# LTC6803_breakout.net
KiCad netlist of a schematic drawn in EAGLE
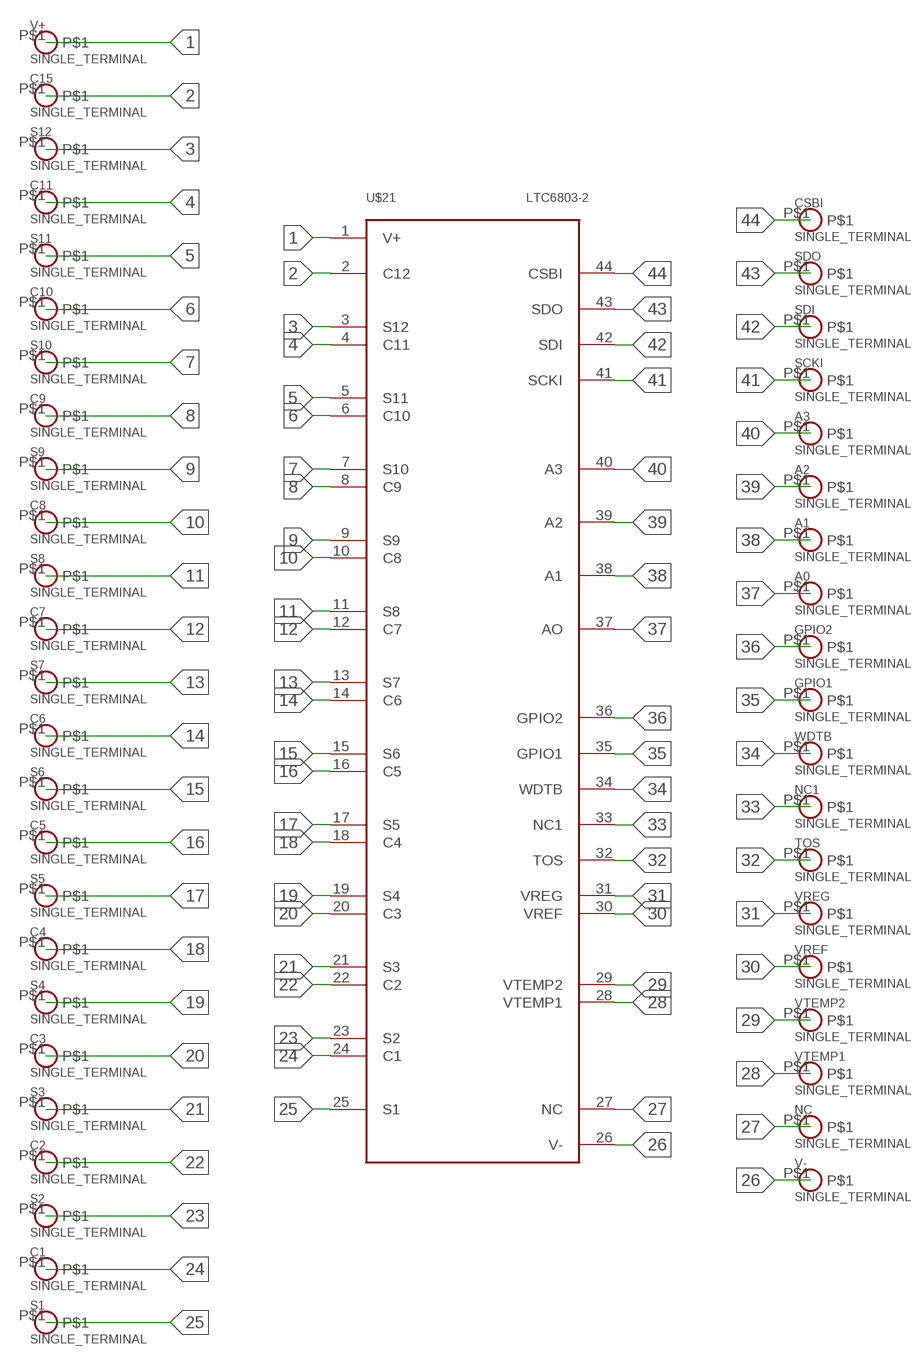
[diagram p0: schematic, sheet 1]

(export (version "E")
  (design (tool "Eeschema 10.0.6"))
  (components
    (comp (ref "A0")
      (value "SINGLE_TERMINAL")
      (footprint "eagle-import:PLATED_HOLE")
      (libsource (lib "eagle-import") (part "SINGLE_TERMINAL"))
    )
    (comp (ref "A1")
      (value "SINGLE_TERMINAL")
      (footprint "eagle-import:PLATED_HOLE")
      (libsource (lib "eagle-import") (part "SINGLE_TERMINAL"))
    )
    (comp (ref "A2")
      (value "SINGLE_TERMINAL")
      (footprint "eagle-import:PLATED_HOLE")
      (libsource (lib "eagle-import") (part "SINGLE_TERMINAL"))
    )
    (comp (ref "A3")
      (value "SINGLE_TERMINAL")
      (footprint "eagle-import:PLATED_HOLE")
      (libsource (lib "eagle-import") (part "SINGLE_TERMINAL"))
    )
    (comp (ref "C1")
      (value "SINGLE_TERMINAL")
      (footprint "eagle-import:PLATED_HOLE")
      (libsource (lib "eagle-import") (part "SINGLE_TERMINAL"))
    )
    (comp (ref "C2")
      (value "SINGLE_TERMINAL")
      (footprint "eagle-import:PLATED_HOLE")
      (libsource (lib "eagle-import") (part "SINGLE_TERMINAL"))
    )
    (comp (ref "C3")
      (value "SINGLE_TERMINAL")
      (footprint "eagle-import:PLATED_HOLE")
      (libsource (lib "eagle-import") (part "SINGLE_TERMINAL"))
    )
    (comp (ref "C4")
      (value "SINGLE_TERMINAL")
      (footprint "eagle-import:PLATED_HOLE")
      (libsource (lib "eagle-import") (part "SINGLE_TERMINAL"))
    )
    (comp (ref "C5")
      (value "SINGLE_TERMINAL")
      (footprint "eagle-import:PLATED_HOLE")
      (libsource (lib "eagle-import") (part "SINGLE_TERMINAL"))
    )
    (comp (ref "C6")
      (value "SINGLE_TERMINAL")
      (footprint "eagle-import:PLATED_HOLE")
      (libsource (lib "eagle-import") (part "SINGLE_TERMINAL"))
    )
    (comp (ref "C7")
      (value "SINGLE_TERMINAL")
      (footprint "eagle-import:PLATED_HOLE")
      (libsource (lib "eagle-import") (part "SINGLE_TERMINAL"))
    )
    (comp (ref "C8")
      (value "SINGLE_TERMINAL")
      (footprint "eagle-import:PLATED_HOLE")
      (libsource (lib "eagle-import") (part "SINGLE_TERMINAL"))
    )
    (comp (ref "C9")
      (value "SINGLE_TERMINAL")
      (footprint "eagle-import:PLATED_HOLE")
      (libsource (lib "eagle-import") (part "SINGLE_TERMINAL"))
    )
    (comp (ref "C10")
      (value "SINGLE_TERMINAL")
      (footprint "eagle-import:PLATED_HOLE")
      (libsource (lib "eagle-import") (part "SINGLE_TERMINAL"))
    )
    (comp (ref "C11")
      (value "SINGLE_TERMINAL")
      (footprint "eagle-import:PLATED_HOLE")
      (libsource (lib "eagle-import") (part "SINGLE_TERMINAL"))
    )
    (comp (ref "C15")
      (value "SINGLE_TERMINAL")
      (footprint "eagle-import:PLATED_HOLE")
      (libsource (lib "eagle-import") (part "SINGLE_TERMINAL"))
    )
    (comp (ref "CSBI")
      (value "SINGLE_TERMINAL")
      (footprint "eagle-import:PLATED_HOLE")
      (libsource (lib "eagle-import") (part "SINGLE_TERMINAL"))
    )
    (comp (ref "GPIO1")
      (value "SINGLE_TERMINAL")
      (footprint "eagle-import:PLATED_HOLE")
      (libsource (lib "eagle-import") (part "SINGLE_TERMINAL"))
    )
    (comp (ref "GPIO2")
      (value "SINGLE_TERMINAL")
      (footprint "eagle-import:PLATED_HOLE")
      (libsource (lib "eagle-import") (part "SINGLE_TERMINAL"))
    )
    (comp (ref "NC")
      (value "SINGLE_TERMINAL")
      (footprint "eagle-import:PLATED_HOLE")
      (libsource (lib "eagle-import") (part "SINGLE_TERMINAL"))
    )
    (comp (ref "NC1")
      (value "SINGLE_TERMINAL")
      (footprint "eagle-import:PLATED_HOLE")
      (libsource (lib "eagle-import") (part "SINGLE_TERMINAL"))
    )
    (comp (ref "S1")
      (value "SINGLE_TERMINAL")
      (footprint "eagle-import:PLATED_HOLE")
      (libsource (lib "eagle-import") (part "SINGLE_TERMINAL"))
    )
    (comp (ref "S2")
      (value "SINGLE_TERMINAL")
      (footprint "eagle-import:PLATED_HOLE")
      (libsource (lib "eagle-import") (part "SINGLE_TERMINAL"))
    )
    (comp (ref "S3")
      (value "SINGLE_TERMINAL")
      (footprint "eagle-import:PLATED_HOLE")
      (libsource (lib "eagle-import") (part "SINGLE_TERMINAL"))
    )
    (comp (ref "S4")
      (value "SINGLE_TERMINAL")
      (footprint "eagle-import:PLATED_HOLE")
      (libsource (lib "eagle-import") (part "SINGLE_TERMINAL"))
    )
    (comp (ref "S5")
      (value "SINGLE_TERMINAL")
      (footprint "eagle-import:PLATED_HOLE")
      (libsource (lib "eagle-import") (part "SINGLE_TERMINAL"))
    )
    (comp (ref "S6")
      (value "SINGLE_TERMINAL")
      (footprint "eagle-import:PLATED_HOLE")
      (libsource (lib "eagle-import") (part "SINGLE_TERMINAL"))
    )
    (comp (ref "S7")
      (value "SINGLE_TERMINAL")
      (footprint "eagle-import:PLATED_HOLE")
      (libsource (lib "eagle-import") (part "SINGLE_TERMINAL"))
    )
    (comp (ref "S8")
      (value "SINGLE_TERMINAL")
      (footprint "eagle-import:PLATED_HOLE")
      (libsource (lib "eagle-import") (part "SINGLE_TERMINAL"))
    )
    (comp (ref "S9")
      (value "SINGLE_TERMINAL")
      (footprint "eagle-import:PLATED_HOLE")
      (libsource (lib "eagle-import") (part "SINGLE_TERMINAL"))
    )
    (comp (ref "S10")
      (value "SINGLE_TERMINAL")
      (footprint "eagle-import:PLATED_HOLE")
      (libsource (lib "eagle-import") (part "SINGLE_TERMINAL"))
    )
    (comp (ref "S11")
      (value "SINGLE_TERMINAL")
      (footprint "eagle-import:PLATED_HOLE")
      (libsource (lib "eagle-import") (part "SINGLE_TERMINAL"))
    )
    (comp (ref "S12")
      (value "SINGLE_TERMINAL")
      (footprint "eagle-import:PLATED_HOLE")
      (libsource (lib "eagle-import") (part "SINGLE_TERMINAL"))
    )
    (comp (ref "SCKI")
      (value "SINGLE_TERMINAL")
      (footprint "eagle-import:PLATED_HOLE")
      (libsource (lib "eagle-import") (part "SINGLE_TERMINAL"))
    )
    (comp (ref "SDI")
      (value "SINGLE_TERMINAL")
      (footprint "eagle-import:PLATED_HOLE")
      (libsource (lib "eagle-import") (part "SINGLE_TERMINAL"))
    )
    (comp (ref "SDO")
      (value "SINGLE_TERMINAL")
      (footprint "eagle-import:PLATED_HOLE")
      (libsource (lib "eagle-import") (part "SINGLE_TERMINAL"))
    )
    (comp (ref "TOS")
      (value "SINGLE_TERMINAL")
      (footprint "eagle-import:PLATED_HOLE")
      (libsource (lib "eagle-import") (part "SINGLE_TERMINAL"))
    )
    (comp (ref "U$21")
      (value "LTC6803-2")
      (footprint "eagle-import:FSOP-44")
      (libsource (lib "eagle-import") (part "LTC6803-2"))
    )
    (comp (ref "V+")
      (value "SINGLE_TERMINAL")
      (footprint "eagle-import:PLATED_HOLE")
      (libsource (lib "eagle-import") (part "SINGLE_TERMINAL"))
    )
    (comp (ref "V-")
      (value "SINGLE_TERMINAL")
      (footprint "eagle-import:PLATED_HOLE")
      (libsource (lib "eagle-import") (part "SINGLE_TERMINAL"))
    )
    (comp (ref "VREF")
      (value "SINGLE_TERMINAL")
      (footprint "eagle-import:PLATED_HOLE")
      (libsource (lib "eagle-import") (part "SINGLE_TERMINAL"))
    )
    (comp (ref "VREG")
      (value "SINGLE_TERMINAL")
      (footprint "eagle-import:PLATED_HOLE")
      (libsource (lib "eagle-import") (part "SINGLE_TERMINAL"))
    )
    (comp (ref "VTEMP1")
      (value "SINGLE_TERMINAL")
      (footprint "eagle-import:PLATED_HOLE")
      (libsource (lib "eagle-import") (part "SINGLE_TERMINAL"))
    )
    (comp (ref "VTEMP2")
      (value "SINGLE_TERMINAL")
      (footprint "eagle-import:PLATED_HOLE")
      (libsource (lib "eagle-import") (part "SINGLE_TERMINAL"))
    )
    (comp (ref "WDTB")
      (value "SINGLE_TERMINAL")
      (footprint "eagle-import:PLATED_HOLE")
      (libsource (lib "eagle-import") (part "SINGLE_TERMINAL"))
    )
  )
  (nets
    (net (code "1") (name "1") (class "Default")
      (node (ref "U$21") (pin "1") (pinfunction "V+_1") (pintype "bidirectional"))
      (node (ref "V+") (pin "P$1") (pinfunction "P$1_P$1") (pintype "bidirectional"))
    )
    (net (code "2") (name "2") (class "Default")
      (node (ref "C15") (pin "P$1") (pinfunction "P$1_P$1") (pintype "bidirectional"))
      (node (ref "U$21") (pin "2") (pinfunction "C12_2") (pintype "bidirectional"))
    )
    (net (code "3") (name "3") (class "Default")
      (node (ref "S12") (pin "P$1") (pinfunction "P$1_P$1") (pintype "bidirectional"))
      (node (ref "U$21") (pin "3") (pinfunction "S12_3") (pintype "bidirectional"))
    )
    (net (code "4") (name "4") (class "Default")
      (node (ref "C11") (pin "P$1") (pinfunction "P$1_P$1") (pintype "bidirectional"))
      (node (ref "U$21") (pin "4") (pinfunction "C11_4") (pintype "bidirectional"))
    )
    (net (code "5") (name "5") (class "Default")
      (node (ref "S11") (pin "P$1") (pinfunction "P$1_P$1") (pintype "bidirectional"))
      (node (ref "U$21") (pin "5") (pinfunction "S11_5") (pintype "bidirectional"))
    )
    (net (code "6") (name "6") (class "Default")
      (node (ref "C10") (pin "P$1") (pinfunction "P$1_P$1") (pintype "bidirectional"))
      (node (ref "U$21") (pin "6") (pinfunction "C10_6") (pintype "bidirectional"))
    )
    (net (code "7") (name "7") (class "Default")
      (node (ref "S10") (pin "P$1") (pinfunction "P$1_P$1") (pintype "bidirectional"))
      (node (ref "U$21") (pin "7") (pinfunction "S10_7") (pintype "bidirectional"))
    )
    (net (code "8") (name "8") (class "Default")
      (node (ref "C9") (pin "P$1") (pinfunction "P$1_P$1") (pintype "bidirectional"))
      (node (ref "U$21") (pin "8") (pinfunction "C9_8") (pintype "bidirectional"))
    )
    (net (code "9") (name "9") (class "Default")
      (node (ref "S9") (pin "P$1") (pinfunction "P$1_P$1") (pintype "bidirectional"))
      (node (ref "U$21") (pin "9") (pinfunction "S9_9") (pintype "bidirectional"))
    )
    (net (code "10") (name "10") (class "Default")
      (node (ref "C8") (pin "P$1") (pinfunction "P$1_P$1") (pintype "bidirectional"))
      (node (ref "U$21") (pin "10") (pinfunction "C8_10") (pintype "bidirectional"))
    )
    (net (code "11") (name "11") (class "Default")
      (node (ref "S8") (pin "P$1") (pinfunction "P$1_P$1") (pintype "bidirectional"))
      (node (ref "U$21") (pin "11") (pinfunction "S8_11") (pintype "bidirectional"))
    )
    (net (code "12") (name "12") (class "Default")
      (node (ref "C7") (pin "P$1") (pinfunction "P$1_P$1") (pintype "bidirectional"))
      (node (ref "U$21") (pin "12") (pinfunction "C7_12") (pintype "bidirectional"))
    )
    (net (code "13") (name "13") (class "Default")
      (node (ref "S7") (pin "P$1") (pinfunction "P$1_P$1") (pintype "bidirectional"))
      (node (ref "U$21") (pin "13") (pinfunction "S7_13") (pintype "bidirectional"))
    )
    (net (code "14") (name "14") (class "Default")
      (node (ref "C6") (pin "P$1") (pinfunction "P$1_P$1") (pintype "bidirectional"))
      (node (ref "U$21") (pin "14") (pinfunction "C6_14") (pintype "bidirectional"))
    )
    (net (code "15") (name "15") (class "Default")
      (node (ref "S6") (pin "P$1") (pinfunction "P$1_P$1") (pintype "bidirectional"))
      (node (ref "U$21") (pin "15") (pinfunction "S6_15") (pintype "bidirectional"))
    )
    (net (code "16") (name "16") (class "Default")
      (node (ref "C5") (pin "P$1") (pinfunction "P$1_P$1") (pintype "bidirectional"))
      (node (ref "U$21") (pin "16") (pinfunction "C5_16") (pintype "bidirectional"))
    )
    (net (code "17") (name "17") (class "Default")
      (node (ref "S5") (pin "P$1") (pinfunction "P$1_P$1") (pintype "bidirectional"))
      (node (ref "U$21") (pin "17") (pinfunction "S5_17") (pintype "bidirectional"))
    )
    (net (code "18") (name "18") (class "Default")
      (node (ref "C4") (pin "P$1") (pinfunction "P$1_P$1") (pintype "bidirectional"))
      (node (ref "U$21") (pin "18") (pinfunction "C4_18") (pintype "bidirectional"))
    )
    (net (code "19") (name "19") (class "Default")
      (node (ref "S4") (pin "P$1") (pinfunction "P$1_P$1") (pintype "bidirectional"))
      (node (ref "U$21") (pin "19") (pinfunction "S4_19") (pintype "bidirectional"))
    )
    (net (code "20") (name "20") (class "Default")
      (node (ref "C3") (pin "P$1") (pinfunction "P$1_P$1") (pintype "bidirectional"))
      (node (ref "U$21") (pin "20") (pinfunction "C3_20") (pintype "bidirectional"))
    )
    (net (code "21") (name "21") (class "Default")
      (node (ref "S3") (pin "P$1") (pinfunction "P$1_P$1") (pintype "bidirectional"))
      (node (ref "U$21") (pin "21") (pinfunction "S3_21") (pintype "bidirectional"))
    )
    (net (code "22") (name "22") (class "Default")
      (node (ref "C2") (pin "P$1") (pinfunction "P$1_P$1") (pintype "bidirectional"))
      (node (ref "U$21") (pin "22") (pinfunction "C2_22") (pintype "bidirectional"))
    )
    (net (code "23") (name "23") (class "Default")
      (node (ref "S2") (pin "P$1") (pinfunction "P$1_P$1") (pintype "bidirectional"))
      (node (ref "U$21") (pin "23") (pinfunction "S2_23") (pintype "bidirectional"))
    )
    (net (code "24") (name "24") (class "Default")
      (node (ref "C1") (pin "P$1") (pinfunction "P$1_P$1") (pintype "bidirectional"))
      (node (ref "U$21") (pin "24") (pinfunction "C1_24") (pintype "bidirectional"))
    )
    (net (code "25") (name "25") (class "Default")
      (node (ref "S1") (pin "P$1") (pinfunction "P$1_P$1") (pintype "bidirectional"))
      (node (ref "U$21") (pin "25") (pinfunction "S1_25") (pintype "bidirectional"))
    )
    (net (code "26") (name "26") (class "Default")
      (node (ref "U$21") (pin "26") (pinfunction "V-_26") (pintype "bidirectional"))
      (node (ref "V-") (pin "P$1") (pinfunction "P$1_P$1") (pintype "bidirectional"))
    )
    (net (code "27") (name "27") (class "Default")
      (node (ref "NC") (pin "P$1") (pinfunction "P$1_P$1") (pintype "bidirectional"))
      (node (ref "U$21") (pin "27") (pinfunction "NC_27") (pintype "bidirectional"))
    )
    (net (code "28") (name "28") (class "Default")
      (node (ref "U$21") (pin "28") (pinfunction "VTEMP1_28") (pintype "bidirectional"))
      (node (ref "VTEMP1") (pin "P$1") (pinfunction "P$1_P$1") (pintype "bidirectional"))
    )
    (net (code "29") (name "29") (class "Default")
      (node (ref "U$21") (pin "29") (pinfunction "VTEMP2_29") (pintype "bidirectional"))
      (node (ref "VTEMP2") (pin "P$1") (pinfunction "P$1_P$1") (pintype "bidirectional"))
    )
    (net (code "30") (name "30") (class "Default")
      (node (ref "U$21") (pin "30") (pinfunction "VREF_30") (pintype "bidirectional"))
      (node (ref "VREF") (pin "P$1") (pinfunction "P$1_P$1") (pintype "bidirectional"))
    )
    (net (code "31") (name "31") (class "Default")
      (node (ref "U$21") (pin "31") (pinfunction "VREG_31") (pintype "bidirectional"))
      (node (ref "VREG") (pin "P$1") (pinfunction "P$1_P$1") (pintype "bidirectional"))
    )
    (net (code "32") (name "32") (class "Default")
      (node (ref "TOS") (pin "P$1") (pinfunction "P$1_P$1") (pintype "bidirectional"))
      (node (ref "U$21") (pin "32") (pinfunction "TOS_32") (pintype "bidirectional"))
    )
    (net (code "33") (name "33") (class "Default")
      (node (ref "NC1") (pin "P$1") (pinfunction "P$1_P$1") (pintype "bidirectional"))
      (node (ref "U$21") (pin "33") (pinfunction "NC1_33") (pintype "bidirectional"))
    )
    (net (code "34") (name "34") (class "Default")
      (node (ref "U$21") (pin "34") (pinfunction "WDTB_34") (pintype "bidirectional"))
      (node (ref "WDTB") (pin "P$1") (pinfunction "P$1_P$1") (pintype "bidirectional"))
    )
    (net (code "35") (name "35") (class "Default")
      (node (ref "GPIO1") (pin "P$1") (pinfunction "P$1_P$1") (pintype "bidirectional"))
      (node (ref "U$21") (pin "35") (pinfunction "GPIO1_35") (pintype "bidirectional"))
    )
    (net (code "36") (name "36") (class "Default")
      (node (ref "GPIO2") (pin "P$1") (pinfunction "P$1_P$1") (pintype "bidirectional"))
      (node (ref "U$21") (pin "36") (pinfunction "GPIO2_36") (pintype "bidirectional"))
    )
    (net (code "37") (name "37") (class "Default")
      (node (ref "A0") (pin "P$1") (pinfunction "P$1_P$1") (pintype "bidirectional"))
      (node (ref "U$21") (pin "37") (pinfunction "AO_37") (pintype "bidirectional"))
    )
    (net (code "38") (name "38") (class "Default")
      (node (ref "A1") (pin "P$1") (pinfunction "P$1_P$1") (pintype "bidirectional"))
      (node (ref "U$21") (pin "38") (pinfunction "A1_38") (pintype "bidirectional"))
    )
    (net (code "39") (name "39") (class "Default")
      (node (ref "A2") (pin "P$1") (pinfunction "P$1_P$1") (pintype "bidirectional"))
      (node (ref "U$21") (pin "39") (pinfunction "A2_39") (pintype "bidirectional"))
    )
    (net (code "40") (name "40") (class "Default")
      (node (ref "A3") (pin "P$1") (pinfunction "P$1_P$1") (pintype "bidirectional"))
      (node (ref "U$21") (pin "40") (pinfunction "A3_40") (pintype "bidirectional"))
    )
    (net (code "41") (name "41") (class "Default")
      (node (ref "SCKI") (pin "P$1") (pinfunction "P$1_P$1") (pintype "bidirectional"))
      (node (ref "U$21") (pin "41") (pinfunction "SCKI_41") (pintype "bidirectional"))
    )
    (net (code "42") (name "42") (class "Default")
      (node (ref "SDI") (pin "P$1") (pinfunction "P$1_P$1") (pintype "bidirectional"))
      (node (ref "U$21") (pin "42") (pinfunction "SDI_42") (pintype "bidirectional"))
    )
    (net (code "43") (name "43") (class "Default")
      (node (ref "SDO") (pin "P$1") (pinfunction "P$1_P$1") (pintype "bidirectional"))
      (node (ref "U$21") (pin "43") (pinfunction "SDO_43") (pintype "bidirectional"))
    )
    (net (code "44") (name "44") (class "Default")
      (node (ref "CSBI") (pin "P$1") (pinfunction "P$1_P$1") (pintype "bidirectional"))
      (node (ref "U$21") (pin "44") (pinfunction "CSBI_44") (pintype "bidirectional"))
    )
  )
)
